# PICO_Probe_v_2_1.net
KiCad netlist of a schematic drawn in Altium Designer
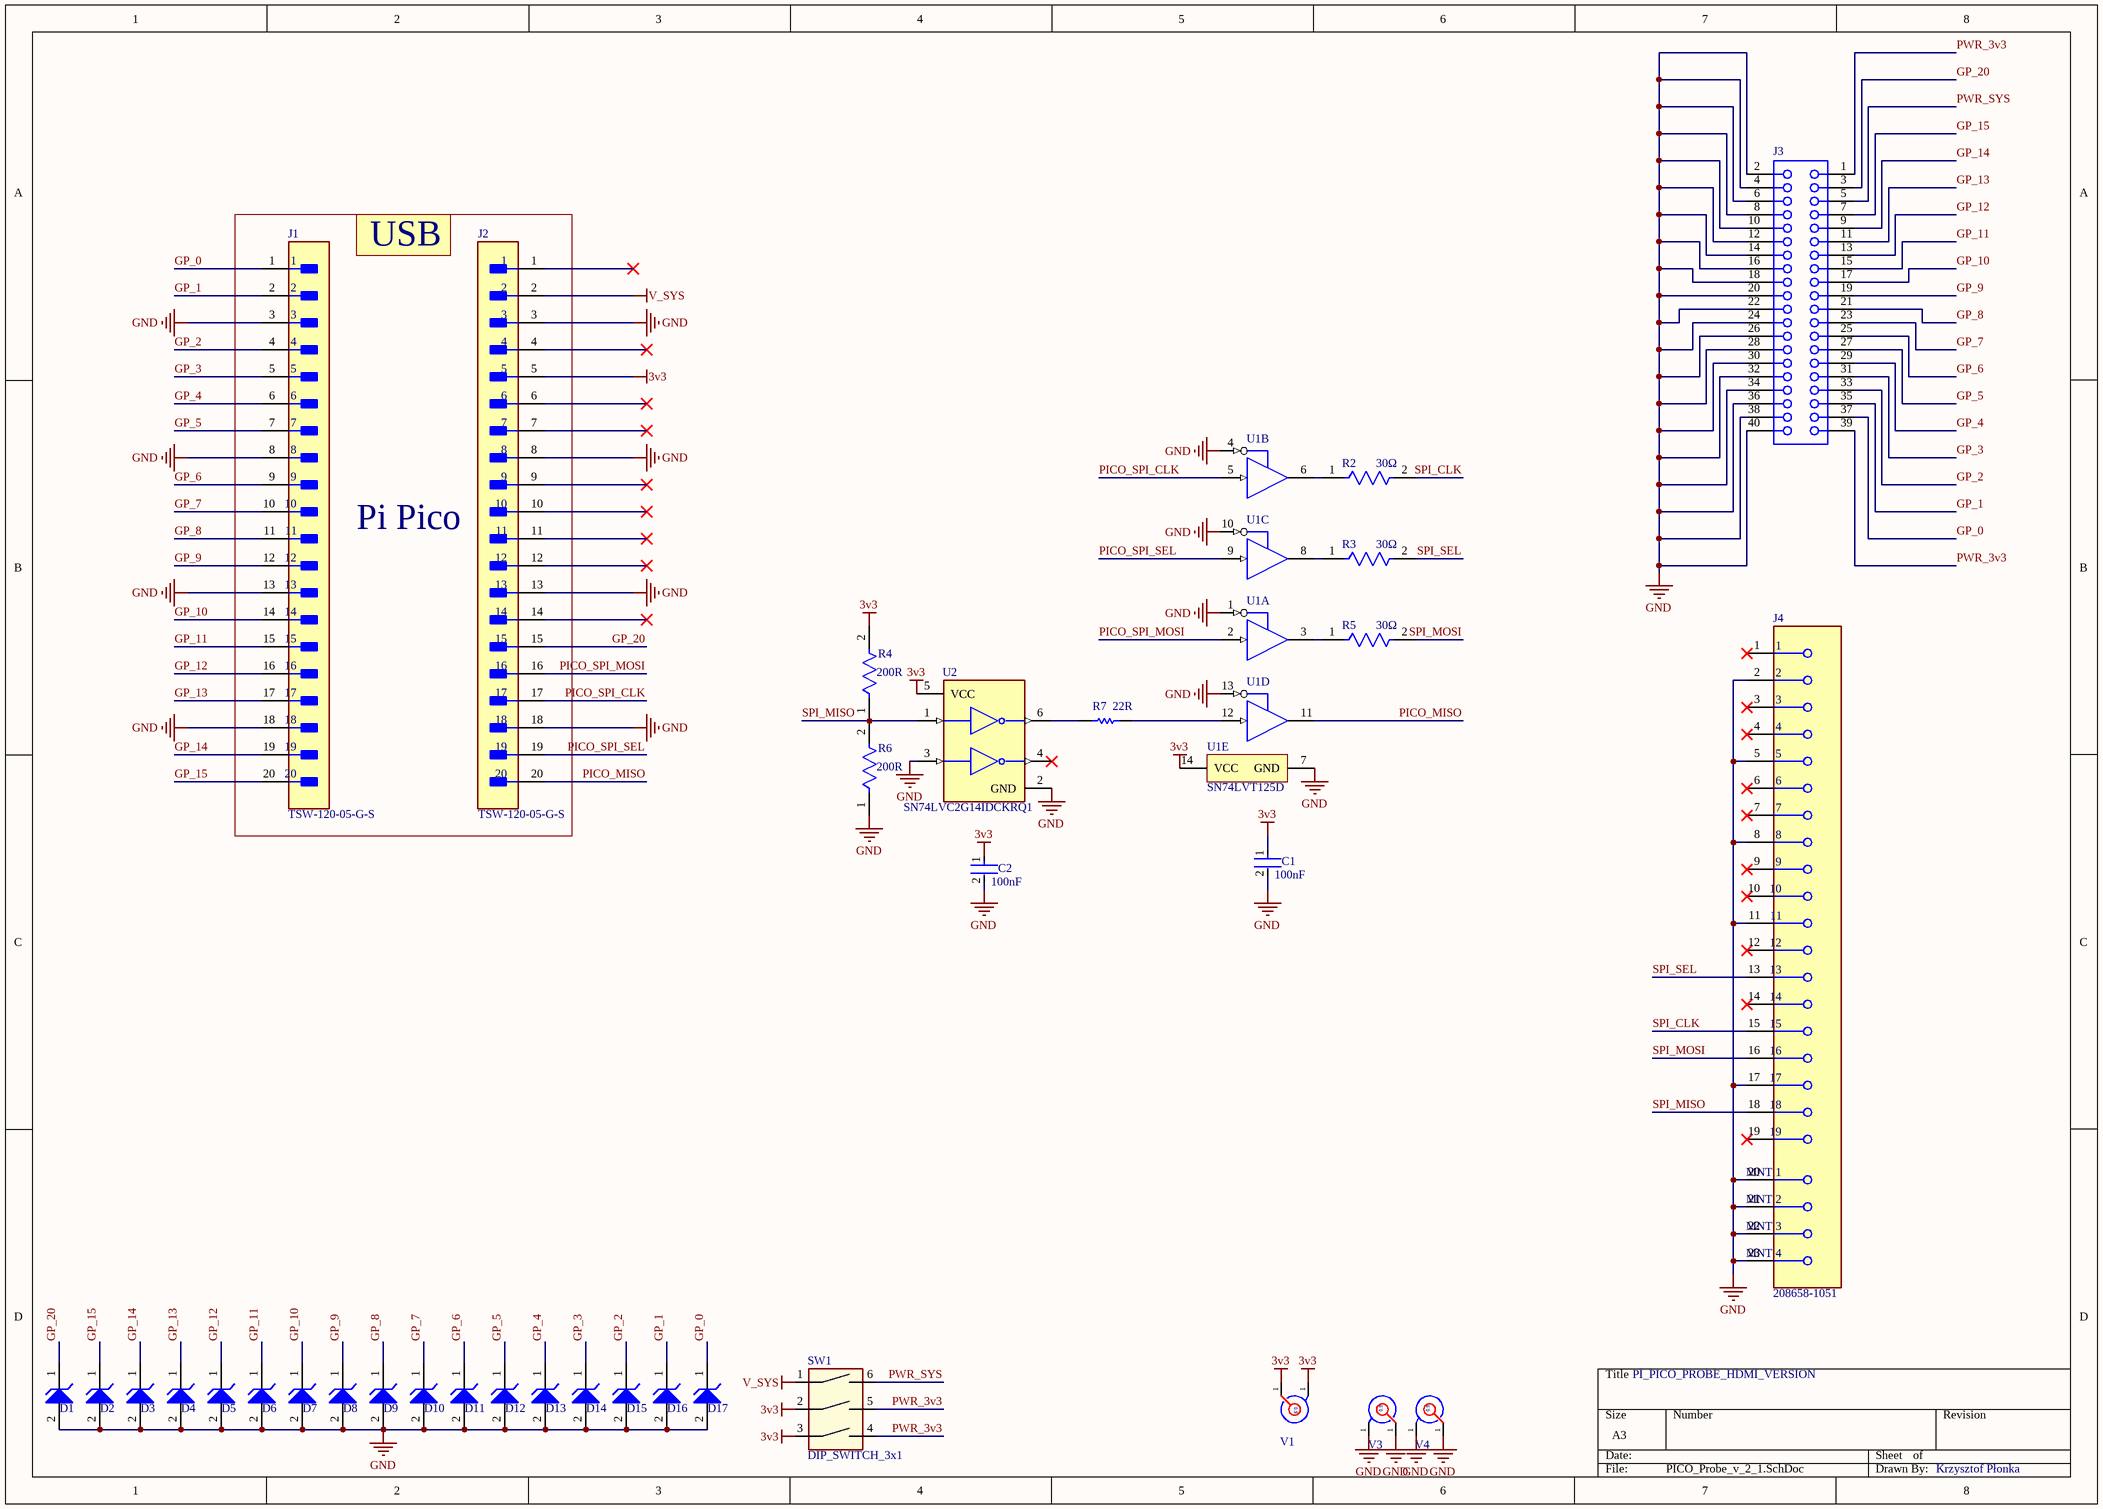
[diagram p0: PICO_Probe_v_2_1.SchDoc]

(export (version "E")
  (design (tool "Eeschema 10.0.6"))
  (components
    (comp (ref "C1")
      (value "100nF")
      (footprint "FP-GRM033-0_03-IPC_A")
      (description "Chip Multilayer Ceramic Capacitors for General Purpose, 0201, 0.10uF, X7R, 15%, 10%, 16V")
      (fields (field (name "Comment") "GRM033Z71C104KE14J"))
      (libsource (lib "Altium Content Vault") (part "b4654b650e69147ec39a6b967a45e02"))
    )
    (comp (ref "C2")
      (value "100nF")
      (footprint "FP-GRM033-0_03-IPC_A")
      (description "Chip Multilayer Ceramic Capacitors for General Purpose, 0201, 0.10uF, X7R, 15%, 10%, 16V")
      (fields (field (name "Comment") "GRM033Z71C104KE14J"))
      (libsource (lib "Altium Content Vault") (part "b4654b650e69147ec39a6b967a45e02"))
    )
    (comp (ref "D1")
      (value "MM5Z3V6T1G")
      (footprint "ONSC-SOD-523-2-502-01_V")
      (description "Zener Voltage Regulator, 500 mW, 2-Pin SOD-523, Pb-Free, Tape and Reel")
      (fields (field (name "MANUFACTURER") "On Semiconductor"))
      (libsource (lib "Altium Content Vault") (part "ONSC-K1A2-2"))
    )
    (comp (ref "D2")
      (value "MM5Z3V6T1G")
      (footprint "ONSC-SOD-523-2-502-01_V")
      (description "Zener Voltage Regulator, 500 mW, 2-Pin SOD-523, Pb-Free, Tape and Reel")
      (fields (field (name "MANUFACTURER") "On Semiconductor"))
      (libsource (lib "Altium Content Vault") (part "ONSC-K1A2-2"))
    )
    (comp (ref "D3")
      (value "MM5Z3V6T1G")
      (footprint "ONSC-SOD-523-2-502-01_V")
      (description "Zener Voltage Regulator, 500 mW, 2-Pin SOD-523, Pb-Free, Tape and Reel")
      (fields (field (name "MANUFACTURER") "On Semiconductor"))
      (libsource (lib "Altium Content Vault") (part "ONSC-K1A2-2"))
    )
    (comp (ref "D4")
      (value "MM5Z3V6T1G")
      (footprint "ONSC-SOD-523-2-502-01_V")
      (description "Zener Voltage Regulator, 500 mW, 2-Pin SOD-523, Pb-Free, Tape and Reel")
      (fields (field (name "MANUFACTURER") "On Semiconductor"))
      (libsource (lib "Altium Content Vault") (part "ONSC-K1A2-2"))
    )
    (comp (ref "D5")
      (value "MM5Z3V6T1G")
      (footprint "ONSC-SOD-523-2-502-01_V")
      (description "Zener Voltage Regulator, 500 mW, 2-Pin SOD-523, Pb-Free, Tape and Reel")
      (fields (field (name "MANUFACTURER") "On Semiconductor"))
      (libsource (lib "Altium Content Vault") (part "ONSC-K1A2-2"))
    )
    (comp (ref "D6")
      (value "MM5Z3V6T1G")
      (footprint "ONSC-SOD-523-2-502-01_V")
      (description "Zener Voltage Regulator, 500 mW, 2-Pin SOD-523, Pb-Free, Tape and Reel")
      (fields (field (name "MANUFACTURER") "On Semiconductor"))
      (libsource (lib "Altium Content Vault") (part "ONSC-K1A2-2"))
    )
    (comp (ref "D7")
      (value "MM5Z3V6T1G")
      (footprint "ONSC-SOD-523-2-502-01_V")
      (description "Zener Voltage Regulator, 500 mW, 2-Pin SOD-523, Pb-Free, Tape and Reel")
      (fields (field (name "MANUFACTURER") "On Semiconductor"))
      (libsource (lib "Altium Content Vault") (part "ONSC-K1A2-2"))
    )
    (comp (ref "D8")
      (value "MM5Z3V6T1G")
      (footprint "ONSC-SOD-523-2-502-01_V")
      (description "Zener Voltage Regulator, 500 mW, 2-Pin SOD-523, Pb-Free, Tape and Reel")
      (fields (field (name "MANUFACTURER") "On Semiconductor"))
      (libsource (lib "Altium Content Vault") (part "ONSC-K1A2-2"))
    )
    (comp (ref "D9")
      (value "MM5Z3V6T1G")
      (footprint "ONSC-SOD-523-2-502-01_V")
      (description "Zener Voltage Regulator, 500 mW, 2-Pin SOD-523, Pb-Free, Tape and Reel")
      (fields (field (name "MANUFACTURER") "On Semiconductor"))
      (libsource (lib "Altium Content Vault") (part "ONSC-K1A2-2"))
    )
    (comp (ref "D10")
      (value "MM5Z3V6T1G")
      (footprint "ONSC-SOD-523-2-502-01_V")
      (description "Zener Voltage Regulator, 500 mW, 2-Pin SOD-523, Pb-Free, Tape and Reel")
      (fields (field (name "MANUFACTURER") "On Semiconductor"))
      (libsource (lib "Altium Content Vault") (part "ONSC-K1A2-2"))
    )
    (comp (ref "D11")
      (value "MM5Z3V6T1G")
      (footprint "ONSC-SOD-523-2-502-01_V")
      (description "Zener Voltage Regulator, 500 mW, 2-Pin SOD-523, Pb-Free, Tape and Reel")
      (fields (field (name "MANUFACTURER") "On Semiconductor"))
      (libsource (lib "Altium Content Vault") (part "ONSC-K1A2-2"))
    )
    (comp (ref "D12")
      (value "MM5Z3V6T1G")
      (footprint "ONSC-SOD-523-2-502-01_V")
      (description "Zener Voltage Regulator, 500 mW, 2-Pin SOD-523, Pb-Free, Tape and Reel")
      (fields (field (name "MANUFACTURER") "On Semiconductor"))
      (libsource (lib "Altium Content Vault") (part "ONSC-K1A2-2"))
    )
    (comp (ref "D13")
      (value "MM5Z3V6T1G")
      (footprint "ONSC-SOD-523-2-502-01_V")
      (description "Zener Voltage Regulator, 500 mW, 2-Pin SOD-523, Pb-Free, Tape and Reel")
      (fields (field (name "MANUFACTURER") "On Semiconductor"))
      (libsource (lib "Altium Content Vault") (part "ONSC-K1A2-2"))
    )
    (comp (ref "D14")
      (value "MM5Z3V6T1G")
      (footprint "ONSC-SOD-523-2-502-01_V")
      (description "Zener Voltage Regulator, 500 mW, 2-Pin SOD-523, Pb-Free, Tape and Reel")
      (fields (field (name "MANUFACTURER") "On Semiconductor"))
      (libsource (lib "Altium Content Vault") (part "ONSC-K1A2-2"))
    )
    (comp (ref "D15")
      (value "MM5Z3V6T1G")
      (footprint "ONSC-SOD-523-2-502-01_V")
      (description "Zener Voltage Regulator, 500 mW, 2-Pin SOD-523, Pb-Free, Tape and Reel")
      (fields (field (name "MANUFACTURER") "On Semiconductor"))
      (libsource (lib "Altium Content Vault") (part "ONSC-K1A2-2"))
    )
    (comp (ref "D16")
      (value "MM5Z3V6T1G")
      (footprint "ONSC-SOD-523-2-502-01_V")
      (description "Zener Voltage Regulator, 500 mW, 2-Pin SOD-523, Pb-Free, Tape and Reel")
      (fields (field (name "MANUFACTURER") "On Semiconductor"))
      (libsource (lib "Altium Content Vault") (part "ONSC-K1A2-2"))
    )
    (comp (ref "D17")
      (value "MM5Z3V6T1G")
      (footprint "ONSC-SOD-523-2-502-01_V")
      (description "Zener Voltage Regulator, 500 mW, 2-Pin SOD-523, Pb-Free, Tape and Reel")
      (fields (field (name "MANUFACTURER") "On Semiconductor"))
      (libsource (lib "Altium Content Vault") (part "ONSC-K1A2-2"))
    )
    (comp (ref "J1")
      (value "TSW-120-05-G-S")
      (footprint "FP-TSW-120-05-G-S-MFG")
      (description "TSW-120-05-G-S Headers & Wire Housings Classic PCB Header Strips, 0.100 pitch")
      (libsource (lib "Altium Content Vault") (part "aa9a6f52efaac70338c2092749629fc"))
    )
    (comp (ref "J2")
      (value "TSW-120-05-G-S")
      (footprint "FP-TSW-120-05-G-S-MFG")
      (description "TSW-120-05-G-S Headers & Wire Housings Classic PCB Header Strips, 0.100 pitch")
      (libsource (lib "Altium Content Vault") (part "aa9a6f52efaac70338c2092749629fc"))
    )
    (comp (ref "J3")
      (value "SSW-120-02-G-D-RA")
      (footprint "SMTC-SSW-120-02-X-D-RA")
      (description "SQ Post Socket, Through-hole, Right Angle, -55 to 125 degC, 2.54 mm Pitch, 40-Pin, Female, RoHS")
      (fields (field (name "MANUFACTURER") "Samtec"))
      (libsource (lib "Altium Content Vault") (part "SMTC-SSW-120-X-X-D"))
    )
    (comp (ref "J4")
      (value "208658-1051")
      (footprint "FP-208658-1051-MFG")
      (description "CONN RCPT HDMI V2.1 19POS SMD RA")
      (libsource (lib "Altium Content Vault") (part "2f8f9bd2e294963b88b490f2f824c1f"))
    )
    (comp (ref "R2")
      (value "ERJ-2RKF30R0X")
      (footprint "FP-ERJ2RK-MFG")
      (fields (field (name "RESISTANCE") "30Ω") (field (name "TOLERANCE") "1%"))
      (libsource (lib "Altium Content Vault") (part "1029c3af85768c4190bb7ad29bc67b5"))
    )
    (comp (ref "R3")
      (value "ERJ-2RKF30R0X")
      (footprint "FP-ERJ2RK-MFG")
      (fields (field (name "RESISTANCE") "30Ω") (field (name "TOLERANCE") "1%"))
      (libsource (lib "Altium Content Vault") (part "1029c3af85768c4190bb7ad29bc67b5"))
    )
    (comp (ref "R4")
      (value "CRCW0402200RFKED")
      (footprint "FP-CRCW0402-e3-IPC_C")
      (description "RES Thick Film, 200Ω, 1%, 0.063W, 100ppm/°C, 0402")
      (fields (field (name "RESISTANCE") "200R") (field (name "TOLERANCE") "1%"))
      (libsource (lib "Altium Content Vault") (part "1029c3af85768c4190bb7ad29bc67b5"))
    )
    (comp (ref "R5")
      (value "ERJ-2RKF30R0X")
      (footprint "FP-ERJ2RK-MFG")
      (fields (field (name "RESISTANCE") "30Ω") (field (name "TOLERANCE") "1%"))
      (libsource (lib "Altium Content Vault") (part "1029c3af85768c4190bb7ad29bc67b5"))
    )
    (comp (ref "R6")
      (value "CRCW0402200RFKED")
      (footprint "FP-CRCW0402-e3-IPC_C")
      (description "RES Thick Film, 200Ω, 1%, 0.063W, 100ppm/°C, 0402")
      (fields (field (name "RESISTANCE") "200R") (field (name "TOLERANCE") "1%"))
      (libsource (lib "Altium Content Vault") (part "1029c3af85768c4190bb7ad29bc67b5"))
    )
    (comp (ref "R7")
      (value "22R")
      (footprint "RESC1005X40X25ML10T10")
      (fields (field (name "PART NUMBER") "CR0402-FX-22R0GLF") (field (name "MANUFACTURER") "Bourns"))
      (libsource (lib "Altium Content Vault") (part "RES"))
    )
    (comp (ref "SW1")
      (value "DIP_SWITCH_3x1")
      (footprint "DIP_SWITCH_3x1")
      (libsource (lib "Schematic-Lib-PhilsLab") (part "DIP_SWITCH_3x1"))
    )
    (comp (ref "U1")
      (value "SN74LVT125D")
      (footprint "D0014A_M")
      (description "3.3-V ABT Quadruple Bus Buffers With 3-State Outputs, D0014A, TUBE")
      (fields
        (field (name "MANUFACTURER") "Texas Instruments")
        (field (name "GENERIC PART NUMBER") "SN74LVT125")
      )
      (libsource (lib "Altium Content Vault") (part "TI-SN74LVT125-D0014A-14"))
    )
    (comp (ref "U2")
      (value "SN74LVC2G14IDCKRQ1")
      (footprint "FP-DCK0006A-MFG")
      (description "IC INVERT SCHMITT 2CH 2IN SC70-6")
      (libsource (lib "Altium Content Vault") (part "a883479e6009d0e4c5ba6ddc194e183"))
    )
    (comp (ref "V1")
      (value "Copper_Via_09")
      (footprint "Copper_Via_09")
      (description "Copper Via 0.9mm hole")
      (libsource (lib "Schematic-Lib-PhilsLab") (part "Copper_Via_09"))
    )
    (comp (ref "V3")
      (value "Copper_Via_09")
      (footprint "Copper_Via_09")
      (description "Copper Via 0.9mm hole")
      (libsource (lib "Schematic-Lib-PhilsLab") (part "Copper_Via_09"))
    )
    (comp (ref "V4")
      (value "Copper_Via_09")
      (footprint "Copper_Via_09")
      (description "Copper Via 0.9mm hole")
      (libsource (lib "Schematic-Lib-PhilsLab") (part "Copper_Via_09"))
    )
  )
  (nets
    (net (code "1") (name "/GP_0") (class "Default")
      (node (ref "D17") (pin "1") (pinfunction "K_1") (pintype "passive"))
      (node (ref "J1") (pin "1") (pinfunction "1_1") (pintype "passive"))
      (node (ref "J3") (pin "37") (pinfunction "37_37") (pintype "passive"))
    )
    (net (code "2") (name "/GP_1") (class "Default")
      (node (ref "D16") (pin "1") (pinfunction "K_1") (pintype "passive"))
      (node (ref "J1") (pin "2") (pinfunction "2_2") (pintype "passive"))
      (node (ref "J3") (pin "35") (pinfunction "35_35") (pintype "passive"))
    )
    (net (code "3") (name "/GP_2") (class "Default")
      (node (ref "D15") (pin "1") (pinfunction "K_1") (pintype "passive"))
      (node (ref "J1") (pin "4") (pinfunction "4_4") (pintype "passive"))
      (node (ref "J3") (pin "33") (pinfunction "33_33") (pintype "passive"))
    )
    (net (code "4") (name "/GP_3") (class "Default")
      (node (ref "D14") (pin "1") (pinfunction "K_1") (pintype "passive"))
      (node (ref "J1") (pin "5") (pinfunction "5_5") (pintype "passive"))
      (node (ref "J3") (pin "31") (pinfunction "31_31") (pintype "passive"))
    )
    (net (code "5") (name "/GP_4") (class "Default")
      (node (ref "D13") (pin "1") (pinfunction "K_1") (pintype "passive"))
      (node (ref "J1") (pin "6") (pinfunction "6_6") (pintype "passive"))
      (node (ref "J3") (pin "29") (pinfunction "29_29") (pintype "passive"))
    )
    (net (code "6") (name "/GP_5") (class "Default")
      (node (ref "D12") (pin "1") (pinfunction "K_1") (pintype "passive"))
      (node (ref "J1") (pin "7") (pinfunction "7_7") (pintype "passive"))
      (node (ref "J3") (pin "27") (pinfunction "27_27") (pintype "passive"))
    )
    (net (code "7") (name "/GP_6") (class "Default")
      (node (ref "D11") (pin "1") (pinfunction "K_1") (pintype "passive"))
      (node (ref "J1") (pin "9") (pinfunction "9_9") (pintype "passive"))
      (node (ref "J3") (pin "25") (pinfunction "25_25") (pintype "passive"))
    )
    (net (code "8") (name "/GP_7") (class "Default")
      (node (ref "D10") (pin "1") (pinfunction "K_1") (pintype "passive"))
      (node (ref "J1") (pin "10") (pinfunction "10_10") (pintype "passive"))
      (node (ref "J3") (pin "23") (pinfunction "23_23") (pintype "passive"))
    )
    (net (code "9") (name "/GP_8") (class "Default")
      (node (ref "D9") (pin "1") (pinfunction "K_1") (pintype "passive"))
      (node (ref "J1") (pin "11") (pinfunction "11_11") (pintype "passive"))
      (node (ref "J3") (pin "21") (pinfunction "21_21") (pintype "passive"))
    )
    (net (code "10") (name "/GP_9") (class "Default")
      (node (ref "D8") (pin "1") (pinfunction "K_1") (pintype "passive"))
      (node (ref "J1") (pin "12") (pinfunction "12_12") (pintype "passive"))
      (node (ref "J3") (pin "19") (pinfunction "19_19") (pintype "passive"))
    )
    (net (code "11") (name "/GP_10") (class "Default")
      (node (ref "D7") (pin "1") (pinfunction "K_1") (pintype "passive"))
      (node (ref "J1") (pin "14") (pinfunction "14_14") (pintype "passive"))
      (node (ref "J3") (pin "17") (pinfunction "17_17") (pintype "passive"))
    )
    (net (code "12") (name "/GP_11") (class "Default")
      (node (ref "D6") (pin "1") (pinfunction "K_1") (pintype "passive"))
      (node (ref "J1") (pin "15") (pinfunction "15_15") (pintype "passive"))
      (node (ref "J3") (pin "15") (pinfunction "15_15") (pintype "passive"))
    )
    (net (code "13") (name "/GP_12") (class "Default")
      (node (ref "D5") (pin "1") (pinfunction "K_1") (pintype "passive"))
      (node (ref "J1") (pin "16") (pinfunction "16_16") (pintype "passive"))
      (node (ref "J3") (pin "13") (pinfunction "13_13") (pintype "passive"))
    )
    (net (code "14") (name "/GP_13") (class "Default")
      (node (ref "D4") (pin "1") (pinfunction "K_1") (pintype "passive"))
      (node (ref "J1") (pin "17") (pinfunction "17_17") (pintype "passive"))
      (node (ref "J3") (pin "11") (pinfunction "11_11") (pintype "passive"))
    )
    (net (code "15") (name "/GP_14") (class "Default")
      (node (ref "D3") (pin "1") (pinfunction "K_1") (pintype "passive"))
      (node (ref "J1") (pin "19") (pinfunction "19_19") (pintype "passive"))
      (node (ref "J3") (pin "9") (pinfunction "9_9") (pintype "passive"))
    )
    (net (code "16") (name "/GP_15") (class "Default")
      (node (ref "D2") (pin "1") (pinfunction "K_1") (pintype "passive"))
      (node (ref "J1") (pin "20") (pinfunction "20_20") (pintype "passive"))
      (node (ref "J3") (pin "7") (pinfunction "7_7") (pintype "passive"))
    )
    (net (code "17") (name "/GP_20") (class "Default")
      (node (ref "D1") (pin "1") (pinfunction "K_1") (pintype "passive"))
      (node (ref "J2") (pin "15") (pinfunction "15_15") (pintype "passive"))
      (node (ref "J3") (pin "3") (pinfunction "3_3") (pintype "passive"))
    )
    (net (code "18") (name "/PICO_MISO") (class "Default")
      (node (ref "J2") (pin "20") (pinfunction "20_20") (pintype "passive"))
      (node (ref "U1") (pin "11") (pinfunction "4Y_11") (pintype "tri_state"))
    )
    (net (code "19") (name "/PICO_SPI_CLK") (class "Default")
      (node (ref "J2") (pin "17") (pinfunction "17_17") (pintype "passive"))
      (node (ref "U1") (pin "5") (pinfunction "2A_5") (pintype "input"))
    )
    (net (code "20") (name "/PICO_SPI_MOSI") (class "Default")
      (node (ref "J2") (pin "16") (pinfunction "16_16") (pintype "passive"))
      (node (ref "U1") (pin "2") (pinfunction "1A_2") (pintype "input"))
    )
    (net (code "21") (name "/PICO_SPI_SEL") (class "Default")
      (node (ref "J2") (pin "19") (pinfunction "19_19") (pintype "passive"))
      (node (ref "U1") (pin "9") (pinfunction "3A_9") (pintype "input"))
    )
    (net (code "22") (name "/PWR_3v3") (class "Default")
      (node (ref "J3") (pin "1") (pinfunction "1_1") (pintype "passive"))
      (node (ref "J3") (pin "39") (pinfunction "39_39") (pintype "passive"))
      (node (ref "SW1") (pin "4") (pinfunction "4_4") (pintype "passive"))
      (node (ref "SW1") (pin "5") (pinfunction "5_5") (pintype "passive"))
    )
    (net (code "23") (name "/PWR_SYS") (class "Default")
      (node (ref "J3") (pin "5") (pinfunction "5_5") (pintype "passive"))
      (node (ref "SW1") (pin "6") (pinfunction "6_6") (pintype "passive"))
    )
    (net (code "24") (name "/SPI_CLK") (class "Default")
      (node (ref "J4") (pin "15") (pinfunction "15_15") (pintype "passive"))
      (node (ref "R2") (pin "2") (pinfunction "2_2") (pintype "passive"))
    )
    (net (code "25") (name "/SPI_MISO") (class "Default")
      (node (ref "J4") (pin "18") (pinfunction "18_18") (pintype "passive"))
      (node (ref "R4") (pin "1") (pinfunction "1_1") (pintype "passive"))
      (node (ref "R6") (pin "2") (pinfunction "2_2") (pintype "passive"))
      (node (ref "U2") (pin "1") (pinfunction "1A_1") (pintype "input"))
    )
    (net (code "26") (name "/SPI_MOSI") (class "Default")
      (node (ref "J4") (pin "16") (pinfunction "16_16") (pintype "passive"))
      (node (ref "R5") (pin "2") (pinfunction "2_2") (pintype "passive"))
    )
    (net (code "27") (name "/SPI_SEL") (class "Default")
      (node (ref "J4") (pin "13") (pinfunction "13_13") (pintype "passive"))
      (node (ref "R3") (pin "2") (pinfunction "2_2") (pintype "passive"))
    )
    (net (code "28") (name "3v3") (class "Default")
      (node (ref "C1") (pin "1") (pinfunction "1_1") (pintype "passive"))
      (node (ref "C2") (pin "1") (pinfunction "1_1") (pintype "passive"))
      (node (ref "J2") (pin "5") (pinfunction "5_5") (pintype "passive"))
      (node (ref "R4") (pin "2") (pinfunction "2_2") (pintype "passive"))
      (node (ref "SW1") (pin "2") (pinfunction "2_2") (pintype "passive"))
      (node (ref "SW1") (pin "3") (pinfunction "3_3") (pintype "passive"))
      (node (ref "U1") (pin "14") (pinfunction "VCC_14") (pintype "power_in"))
      (node (ref "U2") (pin "5") (pinfunction "VCC_5") (pintype "power_in"))
      (node (ref "V1") (pin "1") (pinfunction "1_1") (pintype "passive"))
    )
    (net (code "29") (name "GND") (class "Default")
      (node (ref "C1") (pin "2") (pinfunction "2_2") (pintype "passive"))
      (node (ref "C2") (pin "2") (pinfunction "2_2") (pintype "passive"))
      (node (ref "D1") (pin "2") (pinfunction "A_2") (pintype "passive"))
      (node (ref "D10") (pin "2") (pinfunction "A_2") (pintype "passive"))
      (node (ref "D11") (pin "2") (pinfunction "A_2") (pintype "passive"))
      (node (ref "D12") (pin "2") (pinfunction "A_2") (pintype "passive"))
      (node (ref "D13") (pin "2") (pinfunction "A_2") (pintype "passive"))
      (node (ref "D14") (pin "2") (pinfunction "A_2") (pintype "passive"))
      (node (ref "D15") (pin "2") (pinfunction "A_2") (pintype "passive"))
      (node (ref "D16") (pin "2") (pinfunction "A_2") (pintype "passive"))
      (node (ref "D17") (pin "2") (pinfunction "A_2") (pintype "passive"))
      (node (ref "D2") (pin "2") (pinfunction "A_2") (pintype "passive"))
      (node (ref "D3") (pin "2") (pinfunction "A_2") (pintype "passive"))
      (node (ref "D4") (pin "2") (pinfunction "A_2") (pintype "passive"))
      (node (ref "D5") (pin "2") (pinfunction "A_2") (pintype "passive"))
      (node (ref "D6") (pin "2") (pinfunction "A_2") (pintype "passive"))
      (node (ref "D7") (pin "2") (pinfunction "A_2") (pintype "passive"))
      (node (ref "D8") (pin "2") (pinfunction "A_2") (pintype "passive"))
      (node (ref "D9") (pin "2") (pinfunction "A_2") (pintype "passive"))
      (node (ref "J1") (pin "13") (pinfunction "13_13") (pintype "passive"))
      (node (ref "J1") (pin "18") (pinfunction "18_18") (pintype "passive"))
      (node (ref "J1") (pin "3") (pinfunction "3_3") (pintype "passive"))
      (node (ref "J1") (pin "8") (pinfunction "8_8") (pintype "passive"))
      (node (ref "J2") (pin "13") (pinfunction "13_13") (pintype "passive"))
      (node (ref "J2") (pin "18") (pinfunction "18_18") (pintype "passive"))
      (node (ref "J2") (pin "3") (pinfunction "3_3") (pintype "passive"))
      (node (ref "J2") (pin "8") (pinfunction "8_8") (pintype "passive"))
      (node (ref "J3") (pin "10") (pinfunction "10_10") (pintype "passive"))
      (node (ref "J3") (pin "12") (pinfunction "12_12") (pintype "passive"))
      (node (ref "J3") (pin "14") (pinfunction "14_14") (pintype "passive"))
      (node (ref "J3") (pin "16") (pinfunction "16_16") (pintype "passive"))
      (node (ref "J3") (pin "18") (pinfunction "18_18") (pintype "passive"))
      (node (ref "J3") (pin "2") (pinfunction "2_2") (pintype "passive"))
      (node (ref "J3") (pin "20") (pinfunction "20_20") (pintype "passive"))
      (node (ref "J3") (pin "22") (pinfunction "22_22") (pintype "passive"))
      (node (ref "J3") (pin "24") (pinfunction "24_24") (pintype "passive"))
      (node (ref "J3") (pin "26") (pinfunction "26_26") (pintype "passive"))
      (node (ref "J3") (pin "28") (pinfunction "28_28") (pintype "passive"))
      (node (ref "J3") (pin "30") (pinfunction "30_30") (pintype "passive"))
      (node (ref "J3") (pin "32") (pinfunction "32_32") (pintype "passive"))
      (node (ref "J3") (pin "34") (pinfunction "34_34") (pintype "passive"))
      (node (ref "J3") (pin "36") (pinfunction "36_36") (pintype "passive"))
      (node (ref "J3") (pin "38") (pinfunction "38_38") (pintype "passive"))
      (node (ref "J3") (pin "4") (pinfunction "4_4") (pintype "passive"))
      (node (ref "J3") (pin "40") (pinfunction "40_40") (pintype "passive"))
      (node (ref "J3") (pin "6") (pinfunction "6_6") (pintype "passive"))
      (node (ref "J3") (pin "8") (pinfunction "8_8") (pintype "passive"))
      (node (ref "J4") (pin "11") (pinfunction "11_11") (pintype "passive"))
      (node (ref "J4") (pin "17") (pinfunction "17_17") (pintype "passive"))
      (node (ref "J4") (pin "2") (pinfunction "2_2") (pintype "passive"))
      (node (ref "J4") (pin "20") (pinfunction "MNT_1_20") (pintype "passive"))
      (node (ref "J4") (pin "21") (pinfunction "MNT_2_21") (pintype "passive"))
      (node (ref "J4") (pin "22") (pinfunction "MNT_3_22") (pintype "passive"))
      (node (ref "J4") (pin "23") (pinfunction "MNT_4_23") (pintype "passive"))
      (node (ref "J4") (pin "5") (pinfunction "5_5") (pintype "passive"))
      (node (ref "J4") (pin "8") (pinfunction "8_8") (pintype "passive"))
      (node (ref "R6") (pin "1") (pinfunction "1_1") (pintype "passive"))
      (node (ref "U1") (pin "1") (pinfunction "1~{OE}_1") (pintype "input"))
      (node (ref "U1") (pin "10") (pinfunction "3~{OE}_10") (pintype "input"))
      (node (ref "U1") (pin "13") (pinfunction "4~{OE}_13") (pintype "input"))
      (node (ref "U1") (pin "4") (pinfunction "2~{OE}_4") (pintype "input"))
      (node (ref "U1") (pin "7") (pinfunction "GND_7") (pintype "power_in"))
      (node (ref "U2") (pin "2") (pinfunction "GND_2") (pintype "power_in"))
      (node (ref "U2") (pin "3") (pinfunction "2A_3") (pintype "input"))
      (node (ref "V3") (pin "1") (pinfunction "1_1") (pintype "passive"))
      (node (ref "V4") (pin "1") (pinfunction "1_1") (pintype "passive"))
    )
    (net (code "30") (name "Net-(U1A-1Y)") (class "Default")
      (node (ref "R5") (pin "1") (pinfunction "1_1") (pintype "passive"))
      (node (ref "U1") (pin "3") (pinfunction "1Y_3") (pintype "tri_state"))
    )
    (net (code "31") (name "Net-(U1B-2Y)") (class "Default")
      (node (ref "R2") (pin "1") (pinfunction "1_1") (pintype "passive"))
      (node (ref "U1") (pin "6") (pinfunction "2Y_6") (pintype "tri_state"))
    )
    (net (code "32") (name "Net-(U1C-3Y)") (class "Default")
      (node (ref "R3") (pin "1") (pinfunction "1_1") (pintype "passive"))
      (node (ref "U1") (pin "8") (pinfunction "3Y_8") (pintype "tri_state"))
    )
    (net (code "33") (name "Net-(U1D-4A)") (class "Default")
      (node (ref "R7") (pin "2") (pinfunction "2_2") (pintype "passive"))
      (node (ref "U1") (pin "12") (pinfunction "4A_12") (pintype "input"))
    )
    (net (code "34") (name "Net-(U2-1Y)") (class "Default")
      (node (ref "R7") (pin "1") (pinfunction "1_1") (pintype "passive"))
      (node (ref "U2") (pin "6") (pinfunction "1Y_6") (pintype "output"))
    )
    (net (code "35") (name "V_SYS") (class "Default")
      (node (ref "J2") (pin "2") (pinfunction "2_2") (pintype "passive"))
      (node (ref "SW1") (pin "1") (pinfunction "1_1") (pintype "passive"))
    )
    (net (code "36") (name "unconnected-(J2-Pad1)") (class "Default")
      (node (ref "J2") (pin "1") (pinfunction "1_1") (pintype "passive+no_connect"))
    )
    (net (code "37") (name "unconnected-(J2-Pad4)") (class "Default")
      (node (ref "J2") (pin "4") (pinfunction "4_4") (pintype "passive+no_connect"))
    )
    (net (code "38") (name "unconnected-(J2-Pad6)") (class "Default")
      (node (ref "J2") (pin "6") (pinfunction "6_6") (pintype "passive+no_connect"))
    )
    (net (code "39") (name "unconnected-(J2-Pad7)") (class "Default")
      (node (ref "J2") (pin "7") (pinfunction "7_7") (pintype "passive+no_connect"))
    )
    (net (code "40") (name "unconnected-(J2-Pad9)") (class "Default")
      (node (ref "J2") (pin "9") (pinfunction "9_9") (pintype "passive+no_connect"))
    )
    (net (code "41") (name "unconnected-(J2-Pad10)") (class "Default")
      (node (ref "J2") (pin "10") (pinfunction "10_10") (pintype "passive+no_connect"))
    )
    (net (code "42") (name "unconnected-(J2-Pad11)") (class "Default")
      (node (ref "J2") (pin "11") (pinfunction "11_11") (pintype "passive+no_connect"))
    )
    (net (code "43") (name "unconnected-(J2-Pad12)") (class "Default")
      (node (ref "J2") (pin "12") (pinfunction "12_12") (pintype "passive+no_connect"))
    )
    (net (code "44") (name "unconnected-(J2-Pad14)") (class "Default")
      (node (ref "J2") (pin "14") (pinfunction "14_14") (pintype "passive+no_connect"))
    )
    (net (code "45") (name "unconnected-(J4-Pad1)") (class "Default")
      (node (ref "J4") (pin "1") (pinfunction "1_1") (pintype "passive+no_connect"))
    )
    (net (code "46") (name "unconnected-(J4-Pad3)") (class "Default")
      (node (ref "J4") (pin "3") (pinfunction "3_3") (pintype "passive+no_connect"))
    )
    (net (code "47") (name "unconnected-(J4-Pad4)") (class "Default")
      (node (ref "J4") (pin "4") (pinfunction "4_4") (pintype "passive+no_connect"))
    )
    (net (code "48") (name "unconnected-(J4-Pad6)") (class "Default")
      (node (ref "J4") (pin "6") (pinfunction "6_6") (pintype "passive+no_connect"))
    )
    (net (code "49") (name "unconnected-(J4-Pad7)") (class "Default")
      (node (ref "J4") (pin "7") (pinfunction "7_7") (pintype "passive+no_connect"))
    )
    (net (code "50") (name "unconnected-(J4-Pad9)") (class "Default")
      (node (ref "J4") (pin "9") (pinfunction "9_9") (pintype "passive+no_connect"))
    )
    (net (code "51") (name "unconnected-(J4-Pad10)") (class "Default")
      (node (ref "J4") (pin "10") (pinfunction "10_10") (pintype "passive+no_connect"))
    )
    (net (code "52") (name "unconnected-(J4-Pad12)") (class "Default")
      (node (ref "J4") (pin "12") (pinfunction "12_12") (pintype "passive+no_connect"))
    )
    (net (code "53") (name "unconnected-(J4-Pad14)") (class "Default")
      (node (ref "J4") (pin "14") (pinfunction "14_14") (pintype "passive+no_connect"))
    )
    (net (code "54") (name "unconnected-(J4-Pad19)") (class "Default")
      (node (ref "J4") (pin "19") (pinfunction "19_19") (pintype "passive+no_connect"))
    )
    (net (code "55") (name "unconnected-(U2-2Y-Pad4)") (class "Default")
      (node (ref "U2") (pin "4") (pinfunction "2Y_4") (pintype "output+no_connect"))
    )
  )
)
